# LowPass_Filter.net
KiCad netlist of a schematic drawn in Altium Designer
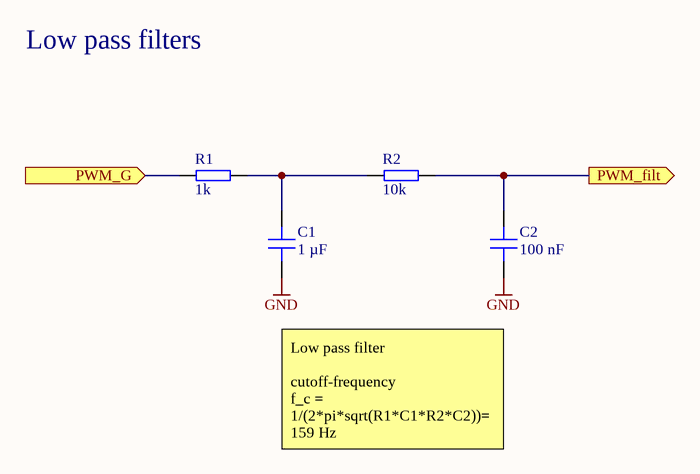
[diagram p0: LowPass_Filter.SchDoc]

(export (version "E")
  (design (tool "Eeschema 10.0.6"))
  (components
    (comp (ref "C1")
      (value "1 µF")
      (footprint "C_0603")
      (description "50V 1uF X7R ±10% 0603 Multilayer Ceramic Capacitors MLCC - SMD/SMT ROHS")
      (fields
        (field (name "MANUFACTURER PART NUMBER") "UMK107AB7105KA-T")
        (field (name "MANUFACTURER") "Taiyo Yuden")
        (field (name "CREATED FROM") "NDiringer")
      )
      (libsource (lib "user") (part "Capacitor"))
    )
    (comp (ref "C2")
      (value "100 nF")
      (footprint "C_0603")
      (description "Capacitor 0603, 50 VDC, 100nF, X7R")
      (fields
        (field (name "MANUFACTURER PART NUMBER") "C0603C104K5RAC3121")
        (field (name "MANUFACTURER") "KEMET")
        (field (name "CREATED FROM") "DHufnagel")
      )
      (libsource (lib "user") (part "Capacitor"))
    )
    (comp (ref "R1")
      (value "1k")
      (footprint "RES 0603_1608")
      (description "SMD resistor 0.1%")
      (fields
        (field (name "MANUFACTURER PART NUMBER") "PCF-W0603LF-03-1001-B-P-LT")
        (field (name "MANUFACTURER") "IRC / TT Electronics")
        (field (name "CREATED FROM") "MGremer")
      )
      (libsource (lib "user") (part "Resistor"))
    )
    (comp (ref "R2")
      (value "10k")
      (footprint "RES 0603_1608")
      (description "SMD resistor 0.1%, 10ppm")
      (fields
        (field (name "MANUFACTURER PART NUMBER") "RQ73C1J10KBTD")
        (field (name "MANUFACTURER") "TE Connectivity")
        (field (name "CREATED FROM") "DHufnagel")
      )
      (libsource (lib "user") (part "Resistor"))
    )
  )
  (nets
    (net (code "1") (name "/PWM_G") (class "Default")
      (node (ref "R1") (pin "1") (pinfunction "1_1") (pintype "passive"))
    )
    (net (code "2") (name "/PWM_filt") (class "Default")
      (node (ref "C2") (pin "2") (pinfunction "2_2") (pintype "passive"))
      (node (ref "R2") (pin "2") (pinfunction "2_2") (pintype "passive"))
    )
    (net (code "3") (name "GND") (class "Default")
      (node (ref "C1") (pin "1") (pinfunction "1_1") (pintype "passive"))
      (node (ref "C2") (pin "1") (pinfunction "1_1") (pintype "passive"))
    )
    (net (code "4") (name "Net-(C1-Pad2)") (class "Default")
      (node (ref "C1") (pin "2") (pinfunction "2_2") (pintype "passive"))
      (node (ref "R1") (pin "2") (pinfunction "2_2") (pintype "passive"))
      (node (ref "R2") (pin "1") (pinfunction "1_1") (pintype "passive"))
    )
  )
)
